# PosiBus.net
KiCad netlist of a schematic drawn in EAGLE
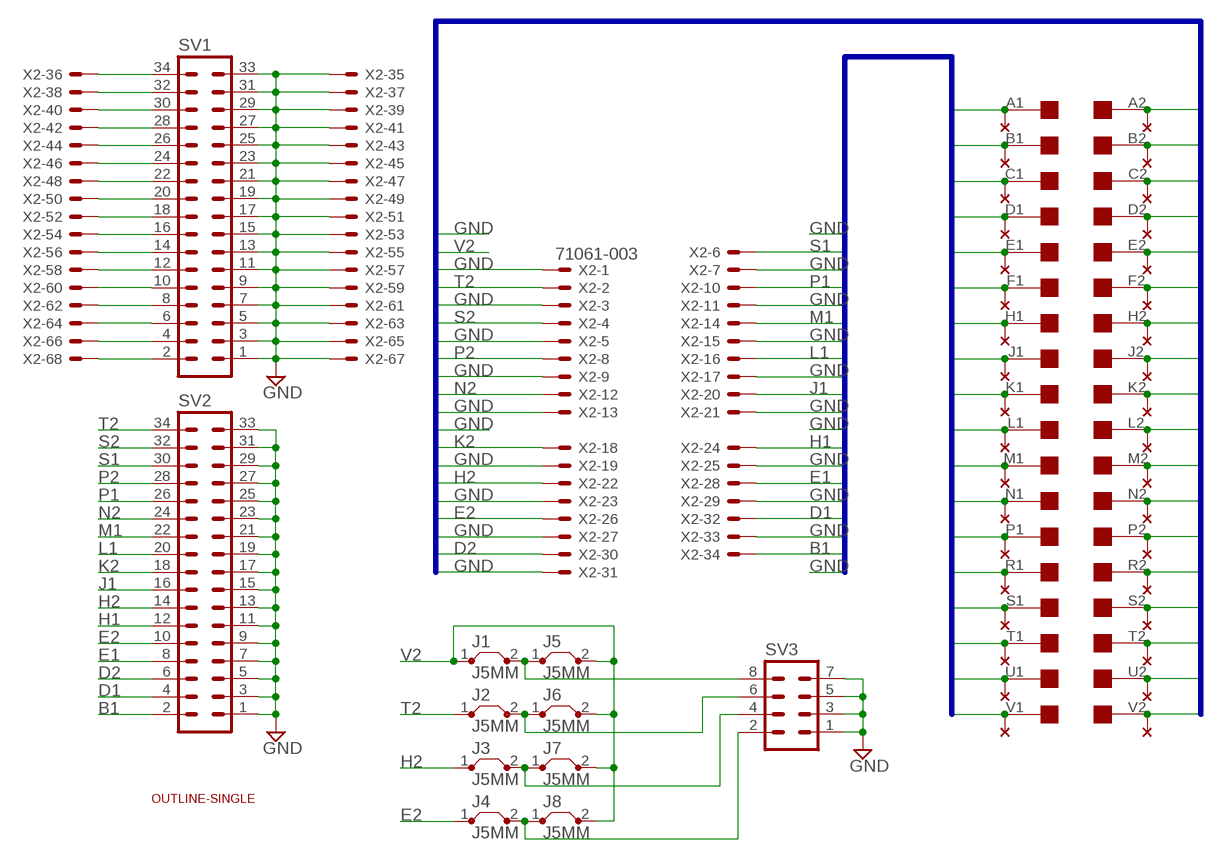
[diagram p0: schematic, sheet 1]

(export (version "E")
  (design (tool "Eeschema 10.0.6"))
  (components
    (comp (ref "EDGE1")
      (value "EDGE-2CONNECTOR")
      (footprint "eagle-import:EDGE-CON2")
      (libsource (lib "eagle-import") (part "EDGE-2CONNECTOR"))
    )
    (comp (ref "J1")
      (value "J5MM")
      (footprint "eagle-import:05")
      (libsource (lib "eagle-import") (part "J5MM"))
    )
    (comp (ref "J2")
      (value "J5MM")
      (footprint "eagle-import:05")
      (libsource (lib "eagle-import") (part "J5MM"))
    )
    (comp (ref "J3")
      (value "J5MM")
      (footprint "eagle-import:05")
      (libsource (lib "eagle-import") (part "J5MM"))
    )
    (comp (ref "J4")
      (value "J5MM")
      (footprint "eagle-import:05")
      (libsource (lib "eagle-import") (part "J5MM"))
    )
    (comp (ref "J5")
      (value "J5MM")
      (footprint "eagle-import:05")
      (libsource (lib "eagle-import") (part "J5MM"))
    )
    (comp (ref "J6")
      (value "J5MM")
      (footprint "eagle-import:05")
      (libsource (lib "eagle-import") (part "J5MM"))
    )
    (comp (ref "J7")
      (value "J5MM")
      (footprint "eagle-import:05")
      (libsource (lib "eagle-import") (part "J5MM"))
    )
    (comp (ref "J8")
      (value "J5MM")
      (footprint "eagle-import:05")
      (libsource (lib "eagle-import") (part "J5MM"))
    )
    (comp (ref "SV1")
      (value "ML34")
      (footprint "eagle-import:ML34")
      (libsource (lib "eagle-import") (part "ML34"))
    )
    (comp (ref "SV2")
      (value "ML34")
      (footprint "eagle-import:ML34")
      (libsource (lib "eagle-import") (part "ML34"))
    )
    (comp (ref "SV3")
      (value "MA04-2")
      (footprint "eagle-import:MA04-2")
      (libsource (lib "eagle-import") (part "MA04-2"))
    )
    (comp (ref "U$2")
      (value "OUTLINE-SINGLE")
      (footprint "eagle-import:SINGLE")
      (libsource (lib "eagle-import") (part "OUTLINE-SINGLE"))
    )
    (comp (ref "U$3")
      (value "THRU-HOLE2")
      (footprint "eagle-import:THRU-HOLEB")
      (libsource (lib "eagle-import") (part "THRU-HOLE2"))
    )
    (comp (ref "X2")
      (value "71061-003")
      (footprint "eagle-import:71061-0003")
      (libsource (lib "eagle-import") (part "71061-003"))
    )
  )
  (nets
    (net (code "1") (name "/B1") (class "Default")
      (node (ref "EDGE1") (pin "B1") (pinfunction "1_B1") (pintype "bidirectional"))
      (node (ref "SV2") (pin "2") (pinfunction "2_2") (pintype "passive"))
      (node (ref "U$3") (pin "B1") (pinfunction "P$1_B1") (pintype "passive"))
      (node (ref "X2") (pin "34") (pinfunction "S_34") (pintype "passive"))
    )
    (net (code "2") (name "/D1") (class "Default")
      (node (ref "EDGE1") (pin "D1") (pinfunction "1_D1") (pintype "bidirectional"))
      (node (ref "SV2") (pin "4") (pinfunction "4_4") (pintype "passive"))
      (node (ref "U$3") (pin "D1") (pinfunction "P$1_D1") (pintype "passive"))
      (node (ref "X2") (pin "32") (pinfunction "S_32") (pintype "passive"))
    )
    (net (code "3") (name "/D2") (class "Default")
      (node (ref "EDGE1") (pin "D2") (pinfunction "1_D2") (pintype "bidirectional"))
      (node (ref "SV2") (pin "6") (pinfunction "6_6") (pintype "passive"))
      (node (ref "U$3") (pin "D2") (pinfunction "P$1_D2") (pintype "passive"))
      (node (ref "X2") (pin "30") (pinfunction "S_30") (pintype "passive"))
    )
    (net (code "4") (name "/E1") (class "Default")
      (node (ref "EDGE1") (pin "E1") (pinfunction "1_E1") (pintype "bidirectional"))
      (node (ref "SV2") (pin "8") (pinfunction "8_8") (pintype "passive"))
      (node (ref "U$3") (pin "E1") (pinfunction "P$1_E1") (pintype "passive"))
      (node (ref "X2") (pin "28") (pinfunction "S_28") (pintype "passive"))
    )
    (net (code "5") (name "/E2") (class "Default")
      (node (ref "EDGE1") (pin "E2") (pinfunction "1_E2") (pintype "bidirectional"))
      (node (ref "J4") (pin "1") (pinfunction "1_1") (pintype "passive"))
      (node (ref "SV2") (pin "10") (pinfunction "10_10") (pintype "passive"))
      (node (ref "U$3") (pin "E2") (pinfunction "P$1_E2") (pintype "passive"))
      (node (ref "X2") (pin "26") (pinfunction "S_26") (pintype "passive"))
    )
    (net (code "6") (name "/H1") (class "Default")
      (node (ref "EDGE1") (pin "H1") (pinfunction "1_H1") (pintype "bidirectional"))
      (node (ref "SV2") (pin "12") (pinfunction "12_12") (pintype "passive"))
      (node (ref "U$3") (pin "H1") (pinfunction "P$1_H1") (pintype "passive"))
      (node (ref "X2") (pin "24") (pinfunction "S_24") (pintype "passive"))
    )
    (net (code "7") (name "/H2") (class "Default")
      (node (ref "EDGE1") (pin "H2") (pinfunction "1_H2") (pintype "bidirectional"))
      (node (ref "J3") (pin "1") (pinfunction "1_1") (pintype "passive"))
      (node (ref "SV2") (pin "14") (pinfunction "14_14") (pintype "passive"))
      (node (ref "U$3") (pin "H2") (pinfunction "P$1_H2") (pintype "passive"))
      (node (ref "X2") (pin "22") (pinfunction "S_22") (pintype "passive"))
    )
    (net (code "8") (name "/J1") (class "Default")
      (node (ref "EDGE1") (pin "J1") (pinfunction "1_J1") (pintype "bidirectional"))
      (node (ref "SV2") (pin "16") (pinfunction "16_16") (pintype "passive"))
      (node (ref "U$3") (pin "J1") (pinfunction "P$1_J1") (pintype "passive"))
      (node (ref "X2") (pin "20") (pinfunction "S_20") (pintype "passive"))
    )
    (net (code "9") (name "/K2") (class "Default")
      (node (ref "EDGE1") (pin "K2") (pinfunction "1_K2") (pintype "bidirectional"))
      (node (ref "SV2") (pin "18") (pinfunction "18_18") (pintype "passive"))
      (node (ref "U$3") (pin "K2") (pinfunction "P$1_K2") (pintype "passive"))
      (node (ref "X2") (pin "18") (pinfunction "S_18") (pintype "passive"))
    )
    (net (code "10") (name "/L1") (class "Default")
      (node (ref "EDGE1") (pin "L1") (pinfunction "1_L1") (pintype "bidirectional"))
      (node (ref "SV2") (pin "20") (pinfunction "20_20") (pintype "passive"))
      (node (ref "U$3") (pin "L1") (pinfunction "P$1_L1") (pintype "passive"))
      (node (ref "X2") (pin "16") (pinfunction "S_16") (pintype "passive"))
    )
    (net (code "11") (name "/M1") (class "Default")
      (node (ref "EDGE1") (pin "M1") (pinfunction "1_M1") (pintype "bidirectional"))
      (node (ref "SV2") (pin "22") (pinfunction "22_22") (pintype "passive"))
      (node (ref "U$3") (pin "M1") (pinfunction "P$1_M1") (pintype "passive"))
      (node (ref "X2") (pin "14") (pinfunction "S_14") (pintype "passive"))
    )
    (net (code "12") (name "/N2") (class "Default")
      (node (ref "EDGE1") (pin "N2") (pinfunction "1_N2") (pintype "bidirectional"))
      (node (ref "SV2") (pin "24") (pinfunction "24_24") (pintype "passive"))
      (node (ref "U$3") (pin "N2") (pinfunction "P$1_N2") (pintype "passive"))
      (node (ref "X2") (pin "12") (pinfunction "S_12") (pintype "passive"))
    )
    (net (code "13") (name "/P1") (class "Default")
      (node (ref "EDGE1") (pin "P1") (pinfunction "1_P1") (pintype "bidirectional"))
      (node (ref "SV2") (pin "26") (pinfunction "26_26") (pintype "passive"))
      (node (ref "U$3") (pin "P1") (pinfunction "P$1_P1") (pintype "passive"))
      (node (ref "X2") (pin "10") (pinfunction "S_10") (pintype "passive"))
    )
    (net (code "14") (name "/P2") (class "Default")
      (node (ref "EDGE1") (pin "P2") (pinfunction "1_P2") (pintype "bidirectional"))
      (node (ref "SV2") (pin "28") (pinfunction "28_28") (pintype "passive"))
      (node (ref "U$3") (pin "P2") (pinfunction "P$1_P2") (pintype "passive"))
      (node (ref "X2") (pin "8") (pinfunction "S_8") (pintype "passive"))
    )
    (net (code "15") (name "/S1") (class "Default")
      (node (ref "EDGE1") (pin "S1") (pinfunction "1_S1") (pintype "bidirectional"))
      (node (ref "SV2") (pin "30") (pinfunction "30_30") (pintype "passive"))
      (node (ref "U$3") (pin "S1") (pinfunction "P$1_S1") (pintype "passive"))
      (node (ref "X2") (pin "6") (pinfunction "S_6") (pintype "passive"))
    )
    (net (code "16") (name "/S2") (class "Default")
      (node (ref "EDGE1") (pin "S2") (pinfunction "1_S2") (pintype "bidirectional"))
      (node (ref "SV2") (pin "32") (pinfunction "32_32") (pintype "passive"))
      (node (ref "U$3") (pin "S2") (pinfunction "P$1_S2") (pintype "passive"))
      (node (ref "X2") (pin "4") (pinfunction "S_4") (pintype "passive"))
    )
    (net (code "17") (name "/T2") (class "Default")
      (node (ref "EDGE1") (pin "T2") (pinfunction "1_T2") (pintype "bidirectional"))
      (node (ref "J2") (pin "1") (pinfunction "1_1") (pintype "passive"))
      (node (ref "SV2") (pin "34") (pinfunction "34_34") (pintype "passive"))
      (node (ref "U$3") (pin "T2") (pinfunction "P$1_T2") (pintype "passive"))
      (node (ref "X2") (pin "2") (pinfunction "S_2") (pintype "passive"))
    )
    (net (code "18") (name "/V2") (class "Default")
      (node (ref "EDGE1") (pin "V2") (pinfunction "1_V2") (pintype "bidirectional"))
      (node (ref "J1") (pin "1") (pinfunction "1_1") (pintype "passive"))
      (node (ref "J5") (pin "2") (pinfunction "2_2") (pintype "passive"))
      (node (ref "J6") (pin "2") (pinfunction "2_2") (pintype "passive"))
      (node (ref "J7") (pin "2") (pinfunction "2_2") (pintype "passive"))
      (node (ref "J8") (pin "2") (pinfunction "2_2") (pintype "passive"))
      (node (ref "U$3") (pin "V2") (pinfunction "P$1_V2") (pintype "passive"))
    )
    (net (code "19") (name "GND") (class "Default")
      (node (ref "EDGE1") (pin "A1") (pinfunction "1_A1") (pintype "bidirectional"))
      (node (ref "EDGE1") (pin "C1") (pinfunction "1_C1") (pintype "bidirectional"))
      (node (ref "EDGE1") (pin "C2") (pinfunction "1_C2") (pintype "bidirectional"))
      (node (ref "EDGE1") (pin "F1") (pinfunction "1_F1") (pintype "bidirectional"))
      (node (ref "EDGE1") (pin "F2") (pinfunction "1_F2") (pintype "bidirectional"))
      (node (ref "EDGE1") (pin "J2") (pinfunction "1_J2") (pintype "bidirectional"))
      (node (ref "EDGE1") (pin "K1") (pinfunction "1_K1") (pintype "bidirectional"))
      (node (ref "EDGE1") (pin "L2") (pinfunction "1_L2") (pintype "bidirectional"))
      (node (ref "EDGE1") (pin "M2") (pinfunction "1_M2") (pintype "bidirectional"))
      (node (ref "EDGE1") (pin "N1") (pinfunction "1_N1") (pintype "bidirectional"))
      (node (ref "EDGE1") (pin "R1") (pinfunction "1_R1") (pintype "bidirectional"))
      (node (ref "EDGE1") (pin "R2") (pinfunction "1_R2") (pintype "bidirectional"))
      (node (ref "EDGE1") (pin "T1") (pinfunction "1_T1") (pintype "bidirectional"))
      (node (ref "EDGE1") (pin "U2") (pinfunction "1_U2") (pintype "bidirectional"))
      (node (ref "SV1") (pin "1") (pinfunction "1_1") (pintype "passive"))
      (node (ref "SV1") (pin "11") (pinfunction "11_11") (pintype "passive"))
      (node (ref "SV1") (pin "13") (pinfunction "13_13") (pintype "passive"))
      (node (ref "SV1") (pin "15") (pinfunction "15_15") (pintype "passive"))
      (node (ref "SV1") (pin "17") (pinfunction "17_17") (pintype "passive"))
      (node (ref "SV1") (pin "19") (pinfunction "19_19") (pintype "passive"))
      (node (ref "SV1") (pin "21") (pinfunction "21_21") (pintype "passive"))
      (node (ref "SV1") (pin "23") (pinfunction "23_23") (pintype "passive"))
      (node (ref "SV1") (pin "25") (pinfunction "25_25") (pintype "passive"))
      (node (ref "SV1") (pin "27") (pinfunction "27_27") (pintype "passive"))
      (node (ref "SV1") (pin "29") (pinfunction "29_29") (pintype "passive"))
      (node (ref "SV1") (pin "3") (pinfunction "3_3") (pintype "passive"))
      (node (ref "SV1") (pin "31") (pinfunction "31_31") (pintype "passive"))
      (node (ref "SV1") (pin "33") (pinfunction "33_33") (pintype "passive"))
      (node (ref "SV1") (pin "5") (pinfunction "5_5") (pintype "passive"))
      (node (ref "SV1") (pin "7") (pinfunction "7_7") (pintype "passive"))
      (node (ref "SV1") (pin "9") (pinfunction "9_9") (pintype "passive"))
      (node (ref "SV2") (pin "1") (pinfunction "1_1") (pintype "passive"))
      (node (ref "SV2") (pin "11") (pinfunction "11_11") (pintype "passive"))
      (node (ref "SV2") (pin "13") (pinfunction "13_13") (pintype "passive"))
      (node (ref "SV2") (pin "15") (pinfunction "15_15") (pintype "passive"))
      (node (ref "SV2") (pin "17") (pinfunction "17_17") (pintype "passive"))
      (node (ref "SV2") (pin "19") (pinfunction "19_19") (pintype "passive"))
      (node (ref "SV2") (pin "21") (pinfunction "21_21") (pintype "passive"))
      (node (ref "SV2") (pin "23") (pinfunction "23_23") (pintype "passive"))
      (node (ref "SV2") (pin "25") (pinfunction "25_25") (pintype "passive"))
      (node (ref "SV2") (pin "27") (pinfunction "27_27") (pintype "passive"))
      (node (ref "SV2") (pin "29") (pinfunction "29_29") (pintype "passive"))
      (node (ref "SV2") (pin "3") (pinfunction "3_3") (pintype "passive"))
      (node (ref "SV2") (pin "31") (pinfunction "31_31") (pintype "passive"))
      (node (ref "SV2") (pin "33") (pinfunction "33_33") (pintype "passive"))
      (node (ref "SV2") (pin "5") (pinfunction "5_5") (pintype "passive"))
      (node (ref "SV2") (pin "7") (pinfunction "7_7") (pintype "passive"))
      (node (ref "SV2") (pin "9") (pinfunction "9_9") (pintype "passive"))
      (node (ref "SV3") (pin "1") (pinfunction "1_1") (pintype "passive"))
      (node (ref "SV3") (pin "3") (pinfunction "3_3") (pintype "passive"))
      (node (ref "SV3") (pin "5") (pinfunction "5_5") (pintype "passive"))
      (node (ref "SV3") (pin "7") (pinfunction "7_7") (pintype "passive"))
      (node (ref "U$3") (pin "A1") (pinfunction "P$1_A1") (pintype "passive"))
      (node (ref "U$3") (pin "C1") (pinfunction "P$1_C1") (pintype "passive"))
      (node (ref "U$3") (pin "C2") (pinfunction "P$1_C2") (pintype "passive"))
      (node (ref "U$3") (pin "F1") (pinfunction "P$1_F1") (pintype "passive"))
      (node (ref "U$3") (pin "F2") (pinfunction "P$1_F2") (pintype "passive"))
      (node (ref "U$3") (pin "J2") (pinfunction "P$1_J2") (pintype "passive"))
      (node (ref "U$3") (pin "K1") (pinfunction "P$1_K1") (pintype "passive"))
      (node (ref "U$3") (pin "L2") (pinfunction "P$1_L2") (pintype "passive"))
      (node (ref "U$3") (pin "M2") (pinfunction "P$1_M2") (pintype "passive"))
      (node (ref "U$3") (pin "N1") (pinfunction "P$1_N1") (pintype "passive"))
      (node (ref "U$3") (pin "R1") (pinfunction "P$1_R1") (pintype "passive"))
      (node (ref "U$3") (pin "R2") (pinfunction "P$1_R2") (pintype "passive"))
      (node (ref "U$3") (pin "T1") (pinfunction "P$1_T1") (pintype "passive"))
      (node (ref "U$3") (pin "U2") (pinfunction "P$1_U2") (pintype "passive"))
      (node (ref "X2") (pin "1") (pinfunction "S_1") (pintype "passive"))
      (node (ref "X2") (pin "11") (pinfunction "S_11") (pintype "passive"))
      (node (ref "X2") (pin "13") (pinfunction "S_13") (pintype "passive"))
      (node (ref "X2") (pin "15") (pinfunction "S_15") (pintype "passive"))
      (node (ref "X2") (pin "17") (pinfunction "S_17") (pintype "passive"))
      (node (ref "X2") (pin "19") (pinfunction "S_19") (pintype "passive"))
      (node (ref "X2") (pin "21") (pinfunction "S_21") (pintype "passive"))
      (node (ref "X2") (pin "23") (pinfunction "S_23") (pintype "passive"))
      (node (ref "X2") (pin "25") (pinfunction "S_25") (pintype "passive"))
      (node (ref "X2") (pin "27") (pinfunction "S_27") (pintype "passive"))
      (node (ref "X2") (pin "29") (pinfunction "S_29") (pintype "passive"))
      (node (ref "X2") (pin "3") (pinfunction "S_3") (pintype "passive"))
      (node (ref "X2") (pin "31") (pinfunction "S_31") (pintype "passive"))
      (node (ref "X2") (pin "33") (pinfunction "S_33") (pintype "passive"))
      (node (ref "X2") (pin "35") (pinfunction "S_35") (pintype "passive"))
      (node (ref "X2") (pin "37") (pinfunction "S_37") (pintype "passive"))
      (node (ref "X2") (pin "39") (pinfunction "S_39") (pintype "passive"))
      (node (ref "X2") (pin "41") (pinfunction "S_41") (pintype "passive"))
      (node (ref "X2") (pin "43") (pinfunction "S_43") (pintype "passive"))
      (node (ref "X2") (pin "45") (pinfunction "S_45") (pintype "passive"))
      (node (ref "X2") (pin "47") (pinfunction "S_47") (pintype "passive"))
      (node (ref "X2") (pin "49") (pinfunction "S_49") (pintype "passive"))
      (node (ref "X2") (pin "5") (pinfunction "S_5") (pintype "passive"))
      (node (ref "X2") (pin "51") (pinfunction "S_51") (pintype "passive"))
      (node (ref "X2") (pin "53") (pinfunction "S_53") (pintype "passive"))
      (node (ref "X2") (pin "55") (pinfunction "S_55") (pintype "passive"))
      (node (ref "X2") (pin "57") (pinfunction "S_57") (pintype "passive"))
      (node (ref "X2") (pin "59") (pinfunction "S_59") (pintype "passive"))
      (node (ref "X2") (pin "61") (pinfunction "S_61") (pintype "passive"))
      (node (ref "X2") (pin "63") (pinfunction "S_63") (pintype "passive"))
      (node (ref "X2") (pin "65") (pinfunction "S_65") (pintype "passive"))
      (node (ref "X2") (pin "67") (pinfunction "S_67") (pintype "passive"))
      (node (ref "X2") (pin "7") (pinfunction "S_7") (pintype "passive"))
      (node (ref "X2") (pin "9") (pinfunction "S_9") (pintype "passive"))
    )
    (net (code "20") (name "Net-(EDGE1AG-1)") (class "Default")
      (node (ref "EDGE1") (pin "U1") (pinfunction "1_U1") (pintype "bidirectional"))
      (node (ref "U$3") (pin "U1") (pinfunction "P$1_U1") (pintype "passive"))
    )
    (net (code "21") (name "Net-(EDGE1AI-1)") (class "Default")
      (node (ref "EDGE1") (pin "V1") (pinfunction "1_V1") (pintype "bidirectional"))
      (node (ref "U$3") (pin "V1") (pinfunction "P$1_V1") (pintype "passive"))
    )
    (net (code "22") (name "Net-(EDGE1B-1)") (class "Default")
      (node (ref "EDGE1") (pin "A2") (pinfunction "1_A2") (pintype "bidirectional"))
      (node (ref "U$3") (pin "A2") (pinfunction "P$1_A2") (pintype "passive"))
    )
    (net (code "23") (name "Net-(EDGE1D-1)") (class "Default")
      (node (ref "EDGE1") (pin "B2") (pinfunction "1_B2") (pintype "bidirectional"))
      (node (ref "U$3") (pin "B2") (pinfunction "P$1_B2") (pintype "passive"))
    )
    (net (code "24") (name "Net-(J1-Pad2)") (class "Default")
      (node (ref "J1") (pin "2") (pinfunction "2_2") (pintype "passive"))
      (node (ref "J5") (pin "1") (pinfunction "1_1") (pintype "passive"))
      (node (ref "SV3") (pin "8") (pinfunction "8_8") (pintype "passive"))
    )
    (net (code "25") (name "Net-(J2-Pad2)") (class "Default")
      (node (ref "J2") (pin "2") (pinfunction "2_2") (pintype "passive"))
      (node (ref "J6") (pin "1") (pinfunction "1_1") (pintype "passive"))
      (node (ref "SV3") (pin "6") (pinfunction "6_6") (pintype "passive"))
    )
    (net (code "26") (name "Net-(J3-Pad2)") (class "Default")
      (node (ref "J3") (pin "2") (pinfunction "2_2") (pintype "passive"))
      (node (ref "J7") (pin "1") (pinfunction "1_1") (pintype "passive"))
      (node (ref "SV3") (pin "4") (pinfunction "4_4") (pintype "passive"))
    )
    (net (code "27") (name "Net-(J4-Pad2)") (class "Default")
      (node (ref "J4") (pin "2") (pinfunction "2_2") (pintype "passive"))
      (node (ref "J8") (pin "1") (pinfunction "1_1") (pintype "passive"))
      (node (ref "SV3") (pin "2") (pinfunction "2_2") (pintype "passive"))
    )
    (net (code "28") (name "Net-(X2AD-S)") (class "Default")
      (node (ref "SV1") (pin "34") (pinfunction "34_34") (pintype "passive"))
      (node (ref "X2") (pin "36") (pinfunction "S_36") (pintype "passive"))
    )
    (net (code "29") (name "Net-(X2AF-S)") (class "Default")
      (node (ref "SV1") (pin "32") (pinfunction "32_32") (pintype "passive"))
      (node (ref "X2") (pin "38") (pinfunction "S_38") (pintype "passive"))
    )
    (net (code "30") (name "Net-(X2AI-S)") (class "Default")
      (node (ref "SV1") (pin "30") (pinfunction "30_30") (pintype "passive"))
      (node (ref "X2") (pin "40") (pinfunction "S_40") (pintype "passive"))
    )
    (net (code "31") (name "Net-(X2AK-S)") (class "Default")
      (node (ref "SV1") (pin "28") (pinfunction "28_28") (pintype "passive"))
      (node (ref "X2") (pin "42") (pinfunction "S_42") (pintype "passive"))
    )
    (net (code "32") (name "Net-(X2AM-S)") (class "Default")
      (node (ref "SV1") (pin "26") (pinfunction "26_26") (pintype "passive"))
      (node (ref "X2") (pin "44") (pinfunction "S_44") (pintype "passive"))
    )
    (net (code "33") (name "Net-(X2AO-S)") (class "Default")
      (node (ref "SV1") (pin "24") (pinfunction "24_24") (pintype "passive"))
      (node (ref "X2") (pin "46") (pinfunction "S_46") (pintype "passive"))
    )
    (net (code "34") (name "Net-(X2AQ-S)") (class "Default")
      (node (ref "SV1") (pin "22") (pinfunction "22_22") (pintype "passive"))
      (node (ref "X2") (pin "48") (pinfunction "S_48") (pintype "passive"))
    )
    (net (code "35") (name "Net-(X2AT-S)") (class "Default")
      (node (ref "SV1") (pin "20") (pinfunction "20_20") (pintype "passive"))
      (node (ref "X2") (pin "50") (pinfunction "S_50") (pintype "passive"))
    )
    (net (code "36") (name "Net-(X2AV-S)") (class "Default")
      (node (ref "SV1") (pin "18") (pinfunction "18_18") (pintype "passive"))
      (node (ref "X2") (pin "52") (pinfunction "S_52") (pintype "passive"))
    )
    (net (code "37") (name "Net-(X2AX-S)") (class "Default")
      (node (ref "SV1") (pin "16") (pinfunction "16_16") (pintype "passive"))
      (node (ref "X2") (pin "54") (pinfunction "S_54") (pintype "passive"))
    )
    (net (code "38") (name "Net-(X2AZ-S)") (class "Default")
      (node (ref "SV1") (pin "14") (pinfunction "14_14") (pintype "passive"))
      (node (ref "X2") (pin "56") (pinfunction "S_56") (pintype "passive"))
    )
    (net (code "39") (name "Net-(X2BB-S)") (class "Default")
      (node (ref "SV1") (pin "12") (pinfunction "12_12") (pintype "passive"))
      (node (ref "X2") (pin "58") (pinfunction "S_58") (pintype "passive"))
    )
    (net (code "40") (name "Net-(X2BE-S)") (class "Default")
      (node (ref "SV1") (pin "10") (pinfunction "10_10") (pintype "passive"))
      (node (ref "X2") (pin "60") (pinfunction "S_60") (pintype "passive"))
    )
    (net (code "41") (name "Net-(X2BG-S)") (class "Default")
      (node (ref "SV1") (pin "8") (pinfunction "8_8") (pintype "passive"))
      (node (ref "X2") (pin "62") (pinfunction "S_62") (pintype "passive"))
    )
    (net (code "42") (name "Net-(X2BI-S)") (class "Default")
      (node (ref "SV1") (pin "6") (pinfunction "6_6") (pintype "passive"))
      (node (ref "X2") (pin "64") (pinfunction "S_64") (pintype "passive"))
    )
    (net (code "43") (name "Net-(X2BK-S)") (class "Default")
      (node (ref "SV1") (pin "4") (pinfunction "4_4") (pintype "passive"))
      (node (ref "X2") (pin "66") (pinfunction "S_66") (pintype "passive"))
    )
    (net (code "44") (name "Net-(X2BM-S)") (class "Default")
      (node (ref "SV1") (pin "2") (pinfunction "2_2") (pintype "passive"))
      (node (ref "X2") (pin "68") (pinfunction "S_68") (pintype "passive"))
    )
  )
)
